# lesion-256.net
KiCad netlist of a schematic drawn in EAGLE
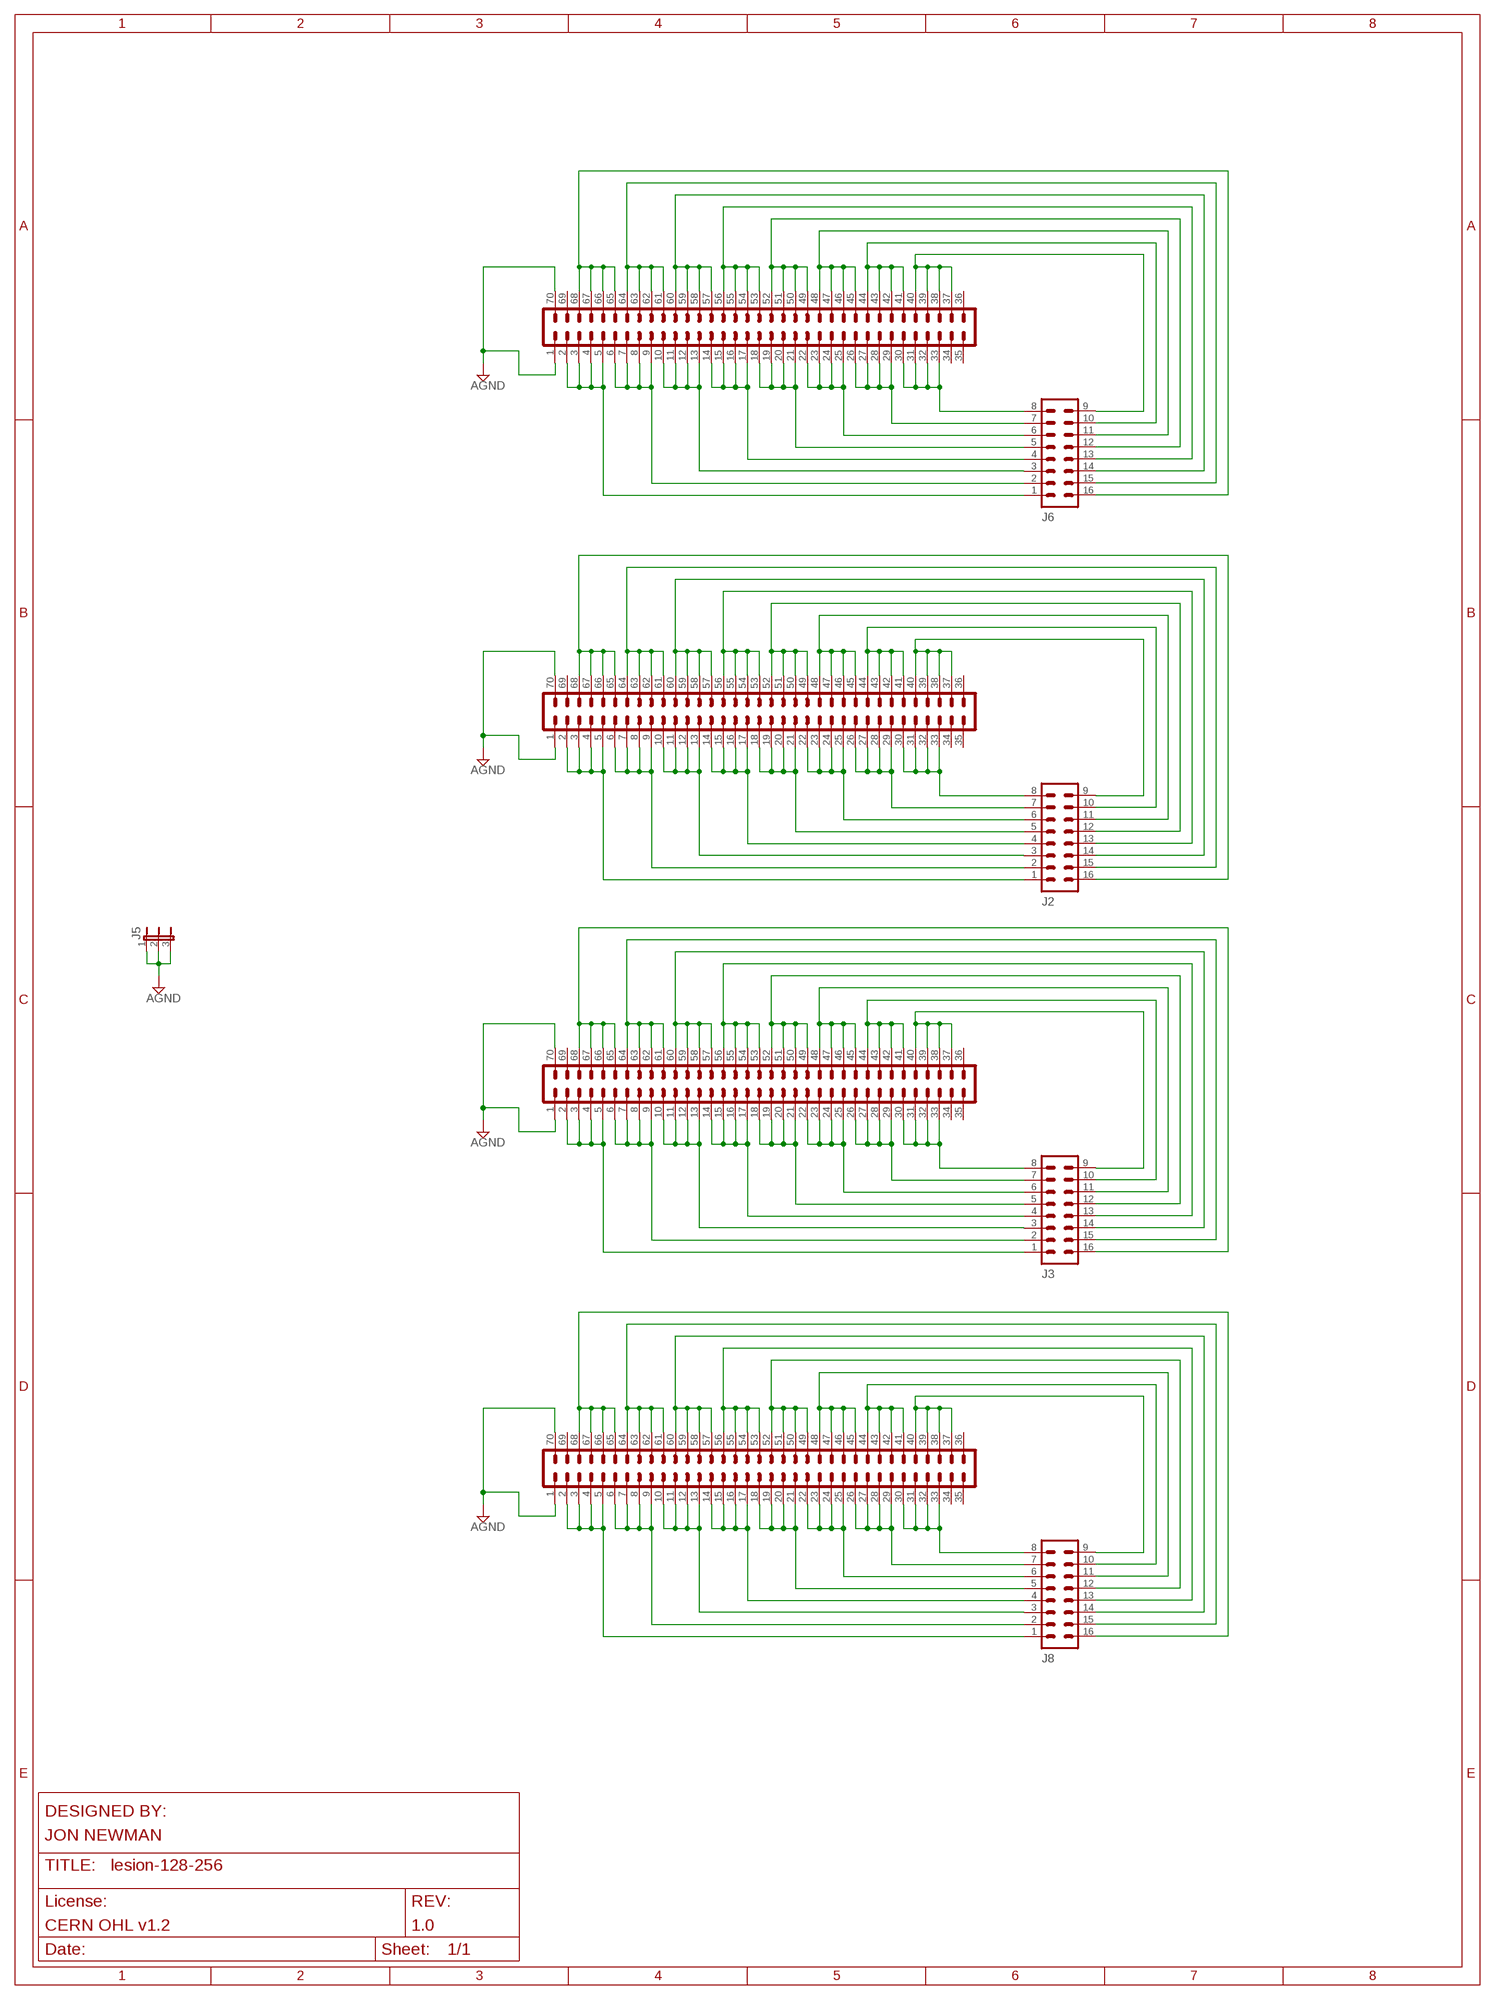
[diagram p0: schematic, sheet 1, part 1 of 2]
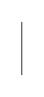
[diagram p1: schematic, sheet 1, part 2 of 2]

(export (version "E")
  (design (tool "Eeschema 10.0.6"))
  (components
    (comp (ref "J2")
      (value "PINHD-2X8_SMD_0.5\"")
      (footprint "eagle-import:JP2X8_SMD_0.5_")
      (libsource (lib "eagle-import") (part "PINHD-2X8_SMD_0.5{dblquote}"))
    )
    (comp (ref "J3")
      (value "PINHD-2X8_SMD_0.5\"")
      (footprint "eagle-import:JP2X8_SMD_0.5_")
      (libsource (lib "eagle-import") (part "PINHD-2X8_SMD_0.5{dblquote}"))
    )
    (comp (ref "J5")
      (value "JP3E_SMD-0.05")
      (footprint "eagle-import:JP3_SMD-0.05")
      (libsource (lib "eagle-import") (part "JP3E_SMD-0.05"))
    )
    (comp (ref "J6")
      (value "PINHD-2X8_SMD_0.5\"")
      (footprint "eagle-import:JP2X8_SMD_0.5_")
      (libsource (lib "eagle-import") (part "PINHD-2X8_SMD_0.5{dblquote}"))
    )
    (comp (ref "J8")
      (value "PINHD-2X8_SMD_0.5\"")
      (footprint "eagle-import:JP2X8_SMD_0.5_")
      (libsource (lib "eagle-import") (part "PINHD-2X8_SMD_0.5{dblquote}"))
    )
    (comp (ref "JA1")
      (value "DF40C(2.0)-70DS-0.4V(51)")
      (footprint "eagle-import:DF40-70REC")
      (libsource (lib "eagle-import") (part "PINHD-2X35_DF40REC"))
    )
    (comp (ref "JA3")
      (value "DF40C(2.0)-70DS-0.4V(51)")
      (footprint "eagle-import:DF40-70REC")
      (libsource (lib "eagle-import") (part "PINHD-2X35_DF40REC"))
    )
    (comp (ref "JA5")
      (value "DF40C(2.0)-70DS-0.4V(51)")
      (footprint "eagle-import:DF40-70REC")
      (libsource (lib "eagle-import") (part "PINHD-2X35_DF40REC"))
    )
    (comp (ref "JA7")
      (value "DF40C(2.0)-70DS-0.4V(51)")
      (footprint "eagle-import:DF40-70REC")
      (libsource (lib "eagle-import") (part "PINHD-2X35_DF40REC"))
    )
  )
  (nets
    (net (code "1") (name "AGND") (class "Default")
      (node (ref "J5") (pin "1") (pinfunction "1_1") (pintype "passive"))
      (node (ref "J5") (pin "2") (pinfunction "2_2") (pintype "passive"))
      (node (ref "J5") (pin "3") (pinfunction "3_3") (pintype "passive"))
      (node (ref "JA1") (pin "1") (pinfunction "1_1") (pintype "bidirectional"))
      (node (ref "JA1") (pin "70") (pinfunction "70_70") (pintype "bidirectional"))
      (node (ref "JA3") (pin "1") (pinfunction "1_1") (pintype "bidirectional"))
      (node (ref "JA3") (pin "70") (pinfunction "70_70") (pintype "bidirectional"))
      (node (ref "JA5") (pin "1") (pinfunction "1_1") (pintype "bidirectional"))
      (node (ref "JA5") (pin "70") (pinfunction "70_70") (pintype "bidirectional"))
      (node (ref "JA7") (pin "1") (pinfunction "1_1") (pintype "bidirectional"))
      (node (ref "JA7") (pin "70") (pinfunction "70_70") (pintype "bidirectional"))
    )
    (net (code "2") (name "Net-(J2-2)") (class "Default")
      (node (ref "J2") (pin "16") (pinfunction "2_16") (pintype "passive"))
      (node (ref "JA1") (pin "65") (pinfunction "65_65") (pintype "bidirectional"))
      (node (ref "JA1") (pin "66") (pinfunction "66_66") (pintype "bidirectional"))
      (node (ref "JA1") (pin "67") (pinfunction "67_67") (pintype "bidirectional"))
      (node (ref "JA1") (pin "68") (pinfunction "68_68") (pintype "bidirectional"))
    )
    (net (code "3") (name "Net-(J2-3)") (class "Default")
      (node (ref "J2") (pin "2") (pinfunction "3_2") (pintype "passive"))
      (node (ref "JA1") (pin "6") (pinfunction "6_6") (pintype "bidirectional"))
      (node (ref "JA1") (pin "7") (pinfunction "7_7") (pintype "bidirectional"))
      (node (ref "JA1") (pin "8") (pinfunction "8_8") (pintype "bidirectional"))
      (node (ref "JA1") (pin "9") (pinfunction "9_9") (pintype "bidirectional"))
    )
    (net (code "4") (name "Net-(J2-4)") (class "Default")
      (node (ref "J2") (pin "15") (pinfunction "4_15") (pintype "passive"))
      (node (ref "JA1") (pin "61") (pinfunction "61_61") (pintype "bidirectional"))
      (node (ref "JA1") (pin "62") (pinfunction "62_62") (pintype "bidirectional"))
      (node (ref "JA1") (pin "63") (pinfunction "63_63") (pintype "bidirectional"))
      (node (ref "JA1") (pin "64") (pinfunction "64_64") (pintype "bidirectional"))
    )
    (net (code "5") (name "Net-(J2-5)") (class "Default")
      (node (ref "J2") (pin "3") (pinfunction "5_3") (pintype "passive"))
      (node (ref "JA1") (pin "10") (pinfunction "10_10") (pintype "bidirectional"))
      (node (ref "JA1") (pin "11") (pinfunction "11_11") (pintype "bidirectional"))
      (node (ref "JA1") (pin "12") (pinfunction "12_12") (pintype "bidirectional"))
      (node (ref "JA1") (pin "13") (pinfunction "13_13") (pintype "bidirectional"))
    )
    (net (code "6") (name "Net-(J2-6)") (class "Default")
      (node (ref "J2") (pin "14") (pinfunction "6_14") (pintype "passive"))
      (node (ref "JA1") (pin "57") (pinfunction "57_57") (pintype "bidirectional"))
      (node (ref "JA1") (pin "58") (pinfunction "58_58") (pintype "bidirectional"))
      (node (ref "JA1") (pin "59") (pinfunction "59_59") (pintype "bidirectional"))
      (node (ref "JA1") (pin "60") (pinfunction "60_60") (pintype "bidirectional"))
    )
    (net (code "7") (name "Net-(J2-7)") (class "Default")
      (node (ref "J2") (pin "4") (pinfunction "7_4") (pintype "passive"))
      (node (ref "JA1") (pin "14") (pinfunction "14_14") (pintype "bidirectional"))
      (node (ref "JA1") (pin "15") (pinfunction "15_15") (pintype "bidirectional"))
      (node (ref "JA1") (pin "16") (pinfunction "16_16") (pintype "bidirectional"))
      (node (ref "JA1") (pin "17") (pinfunction "17_17") (pintype "bidirectional"))
    )
    (net (code "8") (name "Net-(J2-8)") (class "Default")
      (node (ref "J2") (pin "13") (pinfunction "8_13") (pintype "passive"))
      (node (ref "JA1") (pin "53") (pinfunction "53_53") (pintype "bidirectional"))
      (node (ref "JA1") (pin "54") (pinfunction "54_54") (pintype "bidirectional"))
      (node (ref "JA1") (pin "55") (pinfunction "55_55") (pintype "bidirectional"))
      (node (ref "JA1") (pin "56") (pinfunction "56_56") (pintype "bidirectional"))
    )
    (net (code "9") (name "Net-(J2-9)") (class "Default")
      (node (ref "J2") (pin "5") (pinfunction "9_5") (pintype "passive"))
      (node (ref "JA1") (pin "18") (pinfunction "18_18") (pintype "bidirectional"))
      (node (ref "JA1") (pin "19") (pinfunction "19_19") (pintype "bidirectional"))
      (node (ref "JA1") (pin "20") (pinfunction "20_20") (pintype "bidirectional"))
      (node (ref "JA1") (pin "21") (pinfunction "21_21") (pintype "bidirectional"))
    )
    (net (code "10") (name "Net-(J2-10)") (class "Default")
      (node (ref "J2") (pin "12") (pinfunction "10_12") (pintype "passive"))
      (node (ref "JA1") (pin "49") (pinfunction "49_49") (pintype "bidirectional"))
      (node (ref "JA1") (pin "50") (pinfunction "50_50") (pintype "bidirectional"))
      (node (ref "JA1") (pin "51") (pinfunction "51_51") (pintype "bidirectional"))
      (node (ref "JA1") (pin "52") (pinfunction "52_52") (pintype "bidirectional"))
    )
    (net (code "11") (name "Net-(J2-11)") (class "Default")
      (node (ref "J2") (pin "6") (pinfunction "11_6") (pintype "passive"))
      (node (ref "JA1") (pin "22") (pinfunction "22_22") (pintype "bidirectional"))
      (node (ref "JA1") (pin "23") (pinfunction "23_23") (pintype "bidirectional"))
      (node (ref "JA1") (pin "24") (pinfunction "24_24") (pintype "bidirectional"))
      (node (ref "JA1") (pin "25") (pinfunction "25_25") (pintype "bidirectional"))
    )
    (net (code "12") (name "Net-(J2-12)") (class "Default")
      (node (ref "J2") (pin "11") (pinfunction "12_11") (pintype "passive"))
      (node (ref "JA1") (pin "45") (pinfunction "45_45") (pintype "bidirectional"))
      (node (ref "JA1") (pin "46") (pinfunction "46_46") (pintype "bidirectional"))
      (node (ref "JA1") (pin "47") (pinfunction "47_47") (pintype "bidirectional"))
      (node (ref "JA1") (pin "48") (pinfunction "48_48") (pintype "bidirectional"))
    )
    (net (code "13") (name "Net-(J2-13)") (class "Default")
      (node (ref "J2") (pin "7") (pinfunction "13_7") (pintype "passive"))
      (node (ref "JA1") (pin "26") (pinfunction "26_26") (pintype "bidirectional"))
      (node (ref "JA1") (pin "27") (pinfunction "27_27") (pintype "bidirectional"))
      (node (ref "JA1") (pin "28") (pinfunction "28_28") (pintype "bidirectional"))
      (node (ref "JA1") (pin "29") (pinfunction "29_29") (pintype "bidirectional"))
    )
    (net (code "14") (name "Net-(J2-14)") (class "Default")
      (node (ref "J2") (pin "10") (pinfunction "14_10") (pintype "passive"))
      (node (ref "JA1") (pin "41") (pinfunction "41_41") (pintype "bidirectional"))
      (node (ref "JA1") (pin "42") (pinfunction "42_42") (pintype "bidirectional"))
      (node (ref "JA1") (pin "43") (pinfunction "43_43") (pintype "bidirectional"))
      (node (ref "JA1") (pin "44") (pinfunction "44_44") (pintype "bidirectional"))
    )
    (net (code "15") (name "Net-(J2-15)") (class "Default")
      (node (ref "J2") (pin "8") (pinfunction "15_8") (pintype "passive"))
      (node (ref "JA1") (pin "30") (pinfunction "30_30") (pintype "bidirectional"))
      (node (ref "JA1") (pin "31") (pinfunction "31_31") (pintype "bidirectional"))
      (node (ref "JA1") (pin "32") (pinfunction "32_32") (pintype "bidirectional"))
      (node (ref "JA1") (pin "33") (pinfunction "33_33") (pintype "bidirectional"))
    )
    (net (code "16") (name "Net-(J2-16)") (class "Default")
      (node (ref "J2") (pin "9") (pinfunction "16_9") (pintype "passive"))
      (node (ref "JA1") (pin "37") (pinfunction "37_37") (pintype "bidirectional"))
      (node (ref "JA1") (pin "38") (pinfunction "38_38") (pintype "bidirectional"))
      (node (ref "JA1") (pin "39") (pinfunction "39_39") (pintype "bidirectional"))
      (node (ref "JA1") (pin "40") (pinfunction "40_40") (pintype "bidirectional"))
    )
    (net (code "17") (name "Net-(J2-Pad1)") (class "Default")
      (node (ref "J2") (pin "1") (pinfunction "1_1") (pintype "passive"))
      (node (ref "JA1") (pin "2") (pinfunction "2_2") (pintype "bidirectional"))
      (node (ref "JA1") (pin "3") (pinfunction "3_3") (pintype "bidirectional"))
      (node (ref "JA1") (pin "4") (pinfunction "4_4") (pintype "bidirectional"))
      (node (ref "JA1") (pin "5") (pinfunction "5_5") (pintype "bidirectional"))
    )
    (net (code "18") (name "Net-(J3-2)") (class "Default")
      (node (ref "J3") (pin "16") (pinfunction "2_16") (pintype "passive"))
      (node (ref "JA3") (pin "65") (pinfunction "65_65") (pintype "bidirectional"))
      (node (ref "JA3") (pin "66") (pinfunction "66_66") (pintype "bidirectional"))
      (node (ref "JA3") (pin "67") (pinfunction "67_67") (pintype "bidirectional"))
      (node (ref "JA3") (pin "68") (pinfunction "68_68") (pintype "bidirectional"))
    )
    (net (code "19") (name "Net-(J3-3)") (class "Default")
      (node (ref "J3") (pin "2") (pinfunction "3_2") (pintype "passive"))
      (node (ref "JA3") (pin "6") (pinfunction "6_6") (pintype "bidirectional"))
      (node (ref "JA3") (pin "7") (pinfunction "7_7") (pintype "bidirectional"))
      (node (ref "JA3") (pin "8") (pinfunction "8_8") (pintype "bidirectional"))
      (node (ref "JA3") (pin "9") (pinfunction "9_9") (pintype "bidirectional"))
    )
    (net (code "20") (name "Net-(J3-4)") (class "Default")
      (node (ref "J3") (pin "15") (pinfunction "4_15") (pintype "passive"))
      (node (ref "JA3") (pin "61") (pinfunction "61_61") (pintype "bidirectional"))
      (node (ref "JA3") (pin "62") (pinfunction "62_62") (pintype "bidirectional"))
      (node (ref "JA3") (pin "63") (pinfunction "63_63") (pintype "bidirectional"))
      (node (ref "JA3") (pin "64") (pinfunction "64_64") (pintype "bidirectional"))
    )
    (net (code "21") (name "Net-(J3-5)") (class "Default")
      (node (ref "J3") (pin "3") (pinfunction "5_3") (pintype "passive"))
      (node (ref "JA3") (pin "10") (pinfunction "10_10") (pintype "bidirectional"))
      (node (ref "JA3") (pin "11") (pinfunction "11_11") (pintype "bidirectional"))
      (node (ref "JA3") (pin "12") (pinfunction "12_12") (pintype "bidirectional"))
      (node (ref "JA3") (pin "13") (pinfunction "13_13") (pintype "bidirectional"))
    )
    (net (code "22") (name "Net-(J3-6)") (class "Default")
      (node (ref "J3") (pin "14") (pinfunction "6_14") (pintype "passive"))
      (node (ref "JA3") (pin "57") (pinfunction "57_57") (pintype "bidirectional"))
      (node (ref "JA3") (pin "58") (pinfunction "58_58") (pintype "bidirectional"))
      (node (ref "JA3") (pin "59") (pinfunction "59_59") (pintype "bidirectional"))
      (node (ref "JA3") (pin "60") (pinfunction "60_60") (pintype "bidirectional"))
    )
    (net (code "23") (name "Net-(J3-7)") (class "Default")
      (node (ref "J3") (pin "4") (pinfunction "7_4") (pintype "passive"))
      (node (ref "JA3") (pin "14") (pinfunction "14_14") (pintype "bidirectional"))
      (node (ref "JA3") (pin "15") (pinfunction "15_15") (pintype "bidirectional"))
      (node (ref "JA3") (pin "16") (pinfunction "16_16") (pintype "bidirectional"))
      (node (ref "JA3") (pin "17") (pinfunction "17_17") (pintype "bidirectional"))
    )
    (net (code "24") (name "Net-(J3-8)") (class "Default")
      (node (ref "J3") (pin "13") (pinfunction "8_13") (pintype "passive"))
      (node (ref "JA3") (pin "53") (pinfunction "53_53") (pintype "bidirectional"))
      (node (ref "JA3") (pin "54") (pinfunction "54_54") (pintype "bidirectional"))
      (node (ref "JA3") (pin "55") (pinfunction "55_55") (pintype "bidirectional"))
      (node (ref "JA3") (pin "56") (pinfunction "56_56") (pintype "bidirectional"))
    )
    (net (code "25") (name "Net-(J3-9)") (class "Default")
      (node (ref "J3") (pin "5") (pinfunction "9_5") (pintype "passive"))
      (node (ref "JA3") (pin "18") (pinfunction "18_18") (pintype "bidirectional"))
      (node (ref "JA3") (pin "19") (pinfunction "19_19") (pintype "bidirectional"))
      (node (ref "JA3") (pin "20") (pinfunction "20_20") (pintype "bidirectional"))
      (node (ref "JA3") (pin "21") (pinfunction "21_21") (pintype "bidirectional"))
    )
    (net (code "26") (name "Net-(J3-10)") (class "Default")
      (node (ref "J3") (pin "12") (pinfunction "10_12") (pintype "passive"))
      (node (ref "JA3") (pin "49") (pinfunction "49_49") (pintype "bidirectional"))
      (node (ref "JA3") (pin "50") (pinfunction "50_50") (pintype "bidirectional"))
      (node (ref "JA3") (pin "51") (pinfunction "51_51") (pintype "bidirectional"))
      (node (ref "JA3") (pin "52") (pinfunction "52_52") (pintype "bidirectional"))
    )
    (net (code "27") (name "Net-(J3-11)") (class "Default")
      (node (ref "J3") (pin "6") (pinfunction "11_6") (pintype "passive"))
      (node (ref "JA3") (pin "22") (pinfunction "22_22") (pintype "bidirectional"))
      (node (ref "JA3") (pin "23") (pinfunction "23_23") (pintype "bidirectional"))
      (node (ref "JA3") (pin "24") (pinfunction "24_24") (pintype "bidirectional"))
      (node (ref "JA3") (pin "25") (pinfunction "25_25") (pintype "bidirectional"))
    )
    (net (code "28") (name "Net-(J3-12)") (class "Default")
      (node (ref "J3") (pin "11") (pinfunction "12_11") (pintype "passive"))
      (node (ref "JA3") (pin "45") (pinfunction "45_45") (pintype "bidirectional"))
      (node (ref "JA3") (pin "46") (pinfunction "46_46") (pintype "bidirectional"))
      (node (ref "JA3") (pin "47") (pinfunction "47_47") (pintype "bidirectional"))
      (node (ref "JA3") (pin "48") (pinfunction "48_48") (pintype "bidirectional"))
    )
    (net (code "29") (name "Net-(J3-13)") (class "Default")
      (node (ref "J3") (pin "7") (pinfunction "13_7") (pintype "passive"))
      (node (ref "JA3") (pin "26") (pinfunction "26_26") (pintype "bidirectional"))
      (node (ref "JA3") (pin "27") (pinfunction "27_27") (pintype "bidirectional"))
      (node (ref "JA3") (pin "28") (pinfunction "28_28") (pintype "bidirectional"))
      (node (ref "JA3") (pin "29") (pinfunction "29_29") (pintype "bidirectional"))
    )
    (net (code "30") (name "Net-(J3-14)") (class "Default")
      (node (ref "J3") (pin "10") (pinfunction "14_10") (pintype "passive"))
      (node (ref "JA3") (pin "41") (pinfunction "41_41") (pintype "bidirectional"))
      (node (ref "JA3") (pin "42") (pinfunction "42_42") (pintype "bidirectional"))
      (node (ref "JA3") (pin "43") (pinfunction "43_43") (pintype "bidirectional"))
      (node (ref "JA3") (pin "44") (pinfunction "44_44") (pintype "bidirectional"))
    )
    (net (code "31") (name "Net-(J3-15)") (class "Default")
      (node (ref "J3") (pin "8") (pinfunction "15_8") (pintype "passive"))
      (node (ref "JA3") (pin "30") (pinfunction "30_30") (pintype "bidirectional"))
      (node (ref "JA3") (pin "31") (pinfunction "31_31") (pintype "bidirectional"))
      (node (ref "JA3") (pin "32") (pinfunction "32_32") (pintype "bidirectional"))
      (node (ref "JA3") (pin "33") (pinfunction "33_33") (pintype "bidirectional"))
    )
    (net (code "32") (name "Net-(J3-16)") (class "Default")
      (node (ref "J3") (pin "9") (pinfunction "16_9") (pintype "passive"))
      (node (ref "JA3") (pin "37") (pinfunction "37_37") (pintype "bidirectional"))
      (node (ref "JA3") (pin "38") (pinfunction "38_38") (pintype "bidirectional"))
      (node (ref "JA3") (pin "39") (pinfunction "39_39") (pintype "bidirectional"))
      (node (ref "JA3") (pin "40") (pinfunction "40_40") (pintype "bidirectional"))
    )
    (net (code "33") (name "Net-(J3-Pad1)") (class "Default")
      (node (ref "J3") (pin "1") (pinfunction "1_1") (pintype "passive"))
      (node (ref "JA3") (pin "2") (pinfunction "2_2") (pintype "bidirectional"))
      (node (ref "JA3") (pin "3") (pinfunction "3_3") (pintype "bidirectional"))
      (node (ref "JA3") (pin "4") (pinfunction "4_4") (pintype "bidirectional"))
      (node (ref "JA3") (pin "5") (pinfunction "5_5") (pintype "bidirectional"))
    )
    (net (code "34") (name "Net-(J6-2)") (class "Default")
      (node (ref "J6") (pin "16") (pinfunction "2_16") (pintype "passive"))
      (node (ref "JA5") (pin "65") (pinfunction "65_65") (pintype "bidirectional"))
      (node (ref "JA5") (pin "66") (pinfunction "66_66") (pintype "bidirectional"))
      (node (ref "JA5") (pin "67") (pinfunction "67_67") (pintype "bidirectional"))
      (node (ref "JA5") (pin "68") (pinfunction "68_68") (pintype "bidirectional"))
    )
    (net (code "35") (name "Net-(J6-3)") (class "Default")
      (node (ref "J6") (pin "2") (pinfunction "3_2") (pintype "passive"))
      (node (ref "JA5") (pin "6") (pinfunction "6_6") (pintype "bidirectional"))
      (node (ref "JA5") (pin "7") (pinfunction "7_7") (pintype "bidirectional"))
      (node (ref "JA5") (pin "8") (pinfunction "8_8") (pintype "bidirectional"))
      (node (ref "JA5") (pin "9") (pinfunction "9_9") (pintype "bidirectional"))
    )
    (net (code "36") (name "Net-(J6-4)") (class "Default")
      (node (ref "J6") (pin "15") (pinfunction "4_15") (pintype "passive"))
      (node (ref "JA5") (pin "61") (pinfunction "61_61") (pintype "bidirectional"))
      (node (ref "JA5") (pin "62") (pinfunction "62_62") (pintype "bidirectional"))
      (node (ref "JA5") (pin "63") (pinfunction "63_63") (pintype "bidirectional"))
      (node (ref "JA5") (pin "64") (pinfunction "64_64") (pintype "bidirectional"))
    )
    (net (code "37") (name "Net-(J6-5)") (class "Default")
      (node (ref "J6") (pin "3") (pinfunction "5_3") (pintype "passive"))
      (node (ref "JA5") (pin "10") (pinfunction "10_10") (pintype "bidirectional"))
      (node (ref "JA5") (pin "11") (pinfunction "11_11") (pintype "bidirectional"))
      (node (ref "JA5") (pin "12") (pinfunction "12_12") (pintype "bidirectional"))
      (node (ref "JA5") (pin "13") (pinfunction "13_13") (pintype "bidirectional"))
    )
    (net (code "38") (name "Net-(J6-6)") (class "Default")
      (node (ref "J6") (pin "14") (pinfunction "6_14") (pintype "passive"))
      (node (ref "JA5") (pin "57") (pinfunction "57_57") (pintype "bidirectional"))
      (node (ref "JA5") (pin "58") (pinfunction "58_58") (pintype "bidirectional"))
      (node (ref "JA5") (pin "59") (pinfunction "59_59") (pintype "bidirectional"))
      (node (ref "JA5") (pin "60") (pinfunction "60_60") (pintype "bidirectional"))
    )
    (net (code "39") (name "Net-(J6-7)") (class "Default")
      (node (ref "J6") (pin "4") (pinfunction "7_4") (pintype "passive"))
      (node (ref "JA5") (pin "14") (pinfunction "14_14") (pintype "bidirectional"))
      (node (ref "JA5") (pin "15") (pinfunction "15_15") (pintype "bidirectional"))
      (node (ref "JA5") (pin "16") (pinfunction "16_16") (pintype "bidirectional"))
      (node (ref "JA5") (pin "17") (pinfunction "17_17") (pintype "bidirectional"))
    )
    (net (code "40") (name "Net-(J6-8)") (class "Default")
      (node (ref "J6") (pin "13") (pinfunction "8_13") (pintype "passive"))
      (node (ref "JA5") (pin "53") (pinfunction "53_53") (pintype "bidirectional"))
      (node (ref "JA5") (pin "54") (pinfunction "54_54") (pintype "bidirectional"))
      (node (ref "JA5") (pin "55") (pinfunction "55_55") (pintype "bidirectional"))
      (node (ref "JA5") (pin "56") (pinfunction "56_56") (pintype "bidirectional"))
    )
    (net (code "41") (name "Net-(J6-9)") (class "Default")
      (node (ref "J6") (pin "5") (pinfunction "9_5") (pintype "passive"))
      (node (ref "JA5") (pin "18") (pinfunction "18_18") (pintype "bidirectional"))
      (node (ref "JA5") (pin "19") (pinfunction "19_19") (pintype "bidirectional"))
      (node (ref "JA5") (pin "20") (pinfunction "20_20") (pintype "bidirectional"))
      (node (ref "JA5") (pin "21") (pinfunction "21_21") (pintype "bidirectional"))
    )
    (net (code "42") (name "Net-(J6-10)") (class "Default")
      (node (ref "J6") (pin "12") (pinfunction "10_12") (pintype "passive"))
      (node (ref "JA5") (pin "49") (pinfunction "49_49") (pintype "bidirectional"))
      (node (ref "JA5") (pin "50") (pinfunction "50_50") (pintype "bidirectional"))
      (node (ref "JA5") (pin "51") (pinfunction "51_51") (pintype "bidirectional"))
      (node (ref "JA5") (pin "52") (pinfunction "52_52") (pintype "bidirectional"))
    )
    (net (code "43") (name "Net-(J6-11)") (class "Default")
      (node (ref "J6") (pin "6") (pinfunction "11_6") (pintype "passive"))
      (node (ref "JA5") (pin "22") (pinfunction "22_22") (pintype "bidirectional"))
      (node (ref "JA5") (pin "23") (pinfunction "23_23") (pintype "bidirectional"))
      (node (ref "JA5") (pin "24") (pinfunction "24_24") (pintype "bidirectional"))
      (node (ref "JA5") (pin "25") (pinfunction "25_25") (pintype "bidirectional"))
    )
    (net (code "44") (name "Net-(J6-12)") (class "Default")
      (node (ref "J6") (pin "11") (pinfunction "12_11") (pintype "passive"))
      (node (ref "JA5") (pin "45") (pinfunction "45_45") (pintype "bidirectional"))
      (node (ref "JA5") (pin "46") (pinfunction "46_46") (pintype "bidirectional"))
      (node (ref "JA5") (pin "47") (pinfunction "47_47") (pintype "bidirectional"))
      (node (ref "JA5") (pin "48") (pinfunction "48_48") (pintype "bidirectional"))
    )
    (net (code "45") (name "Net-(J6-13)") (class "Default")
      (node (ref "J6") (pin "7") (pinfunction "13_7") (pintype "passive"))
      (node (ref "JA5") (pin "26") (pinfunction "26_26") (pintype "bidirectional"))
      (node (ref "JA5") (pin "27") (pinfunction "27_27") (pintype "bidirectional"))
      (node (ref "JA5") (pin "28") (pinfunction "28_28") (pintype "bidirectional"))
      (node (ref "JA5") (pin "29") (pinfunction "29_29") (pintype "bidirectional"))
    )
    (net (code "46") (name "Net-(J6-14)") (class "Default")
      (node (ref "J6") (pin "10") (pinfunction "14_10") (pintype "passive"))
      (node (ref "JA5") (pin "41") (pinfunction "41_41") (pintype "bidirectional"))
      (node (ref "JA5") (pin "42") (pinfunction "42_42") (pintype "bidirectional"))
      (node (ref "JA5") (pin "43") (pinfunction "43_43") (pintype "bidirectional"))
      (node (ref "JA5") (pin "44") (pinfunction "44_44") (pintype "bidirectional"))
    )
    (net (code "47") (name "Net-(J6-15)") (class "Default")
      (node (ref "J6") (pin "8") (pinfunction "15_8") (pintype "passive"))
      (node (ref "JA5") (pin "30") (pinfunction "30_30") (pintype "bidirectional"))
      (node (ref "JA5") (pin "31") (pinfunction "31_31") (pintype "bidirectional"))
      (node (ref "JA5") (pin "32") (pinfunction "32_32") (pintype "bidirectional"))
      (node (ref "JA5") (pin "33") (pinfunction "33_33") (pintype "bidirectional"))
    )
    (net (code "48") (name "Net-(J6-16)") (class "Default")
      (node (ref "J6") (pin "9") (pinfunction "16_9") (pintype "passive"))
      (node (ref "JA5") (pin "37") (pinfunction "37_37") (pintype "bidirectional"))
      (node (ref "JA5") (pin "38") (pinfunction "38_38") (pintype "bidirectional"))
      (node (ref "JA5") (pin "39") (pinfunction "39_39") (pintype "bidirectional"))
      (node (ref "JA5") (pin "40") (pinfunction "40_40") (pintype "bidirectional"))
    )
    (net (code "49") (name "Net-(J6-Pad1)") (class "Default")
      (node (ref "J6") (pin "1") (pinfunction "1_1") (pintype "passive"))
      (node (ref "JA5") (pin "2") (pinfunction "2_2") (pintype "bidirectional"))
      (node (ref "JA5") (pin "3") (pinfunction "3_3") (pintype "bidirectional"))
      (node (ref "JA5") (pin "4") (pinfunction "4_4") (pintype "bidirectional"))
      (node (ref "JA5") (pin "5") (pinfunction "5_5") (pintype "bidirectional"))
    )
    (net (code "50") (name "Net-(J8-2)") (class "Default")
      (node (ref "J8") (pin "16") (pinfunction "2_16") (pintype "passive"))
      (node (ref "JA7") (pin "65") (pinfunction "65_65") (pintype "bidirectional"))
      (node (ref "JA7") (pin "66") (pinfunction "66_66") (pintype "bidirectional"))
      (node (ref "JA7") (pin "67") (pinfunction "67_67") (pintype "bidirectional"))
      (node (ref "JA7") (pin "68") (pinfunction "68_68") (pintype "bidirectional"))
    )
    (net (code "51") (name "Net-(J8-3)") (class "Default")
      (node (ref "J8") (pin "2") (pinfunction "3_2") (pintype "passive"))
      (node (ref "JA7") (pin "6") (pinfunction "6_6") (pintype "bidirectional"))
      (node (ref "JA7") (pin "7") (pinfunction "7_7") (pintype "bidirectional"))
      (node (ref "JA7") (pin "8") (pinfunction "8_8") (pintype "bidirectional"))
      (node (ref "JA7") (pin "9") (pinfunction "9_9") (pintype "bidirectional"))
    )
    (net (code "52") (name "Net-(J8-4)") (class "Default")
      (node (ref "J8") (pin "15") (pinfunction "4_15") (pintype "passive"))
      (node (ref "JA7") (pin "61") (pinfunction "61_61") (pintype "bidirectional"))
      (node (ref "JA7") (pin "62") (pinfunction "62_62") (pintype "bidirectional"))
      (node (ref "JA7") (pin "63") (pinfunction "63_63") (pintype "bidirectional"))
      (node (ref "JA7") (pin "64") (pinfunction "64_64") (pintype "bidirectional"))
    )
    (net (code "53") (name "Net-(J8-5)") (class "Default")
      (node (ref "J8") (pin "3") (pinfunction "5_3") (pintype "passive"))
      (node (ref "JA7") (pin "10") (pinfunction "10_10") (pintype "bidirectional"))
      (node (ref "JA7") (pin "11") (pinfunction "11_11") (pintype "bidirectional"))
      (node (ref "JA7") (pin "12") (pinfunction "12_12") (pintype "bidirectional"))
      (node (ref "JA7") (pin "13") (pinfunction "13_13") (pintype "bidirectional"))
    )
    (net (code "54") (name "Net-(J8-6)") (class "Default")
      (node (ref "J8") (pin "14") (pinfunction "6_14") (pintype "passive"))
      (node (ref "JA7") (pin "57") (pinfunction "57_57") (pintype "bidirectional"))
      (node (ref "JA7") (pin "58") (pinfunction "58_58") (pintype "bidirectional"))
      (node (ref "JA7") (pin "59") (pinfunction "59_59") (pintype "bidirectional"))
      (node (ref "JA7") (pin "60") (pinfunction "60_60") (pintype "bidirectional"))
    )
    (net (code "55") (name "Net-(J8-7)") (class "Default")
      (node (ref "J8") (pin "4") (pinfunction "7_4") (pintype "passive"))
      (node (ref "JA7") (pin "14") (pinfunction "14_14") (pintype "bidirectional"))
      (node (ref "JA7") (pin "15") (pinfunction "15_15") (pintype "bidirectional"))
      (node (ref "JA7") (pin "16") (pinfunction "16_16") (pintype "bidirectional"))
      (node (ref "JA7") (pin "17") (pinfunction "17_17") (pintype "bidirectional"))
    )
    (net (code "56") (name "Net-(J8-8)") (class "Default")
      (node (ref "J8") (pin "13") (pinfunction "8_13") (pintype "passive"))
      (node (ref "JA7") (pin "53") (pinfunction "53_53") (pintype "bidirectional"))
      (node (ref "JA7") (pin "54") (pinfunction "54_54") (pintype "bidirectional"))
      (node (ref "JA7") (pin "55") (pinfunction "55_55") (pintype "bidirectional"))
      (node (ref "JA7") (pin "56") (pinfunction "56_56") (pintype "bidirectional"))
    )
    (net (code "57") (name "Net-(J8-9)") (class "Default")
      (node (ref "J8") (pin "5") (pinfunction "9_5") (pintype "passive"))
      (node (ref "JA7") (pin "18") (pinfunction "18_18") (pintype "bidirectional"))
      (node (ref "JA7") (pin "19") (pinfunction "19_19") (pintype "bidirectional"))
      (node (ref "JA7") (pin "20") (pinfunction "20_20") (pintype "bidirectional"))
      (node (ref "JA7") (pin "21") (pinfunction "21_21") (pintype "bidirectional"))
    )
    (net (code "58") (name "Net-(J8-10)") (class "Default")
      (node (ref "J8") (pin "12") (pinfunction "10_12") (pintype "passive"))
      (node (ref "JA7") (pin "49") (pinfunction "49_49") (pintype "bidirectional"))
      (node (ref "JA7") (pin "50") (pinfunction "50_50") (pintype "bidirectional"))
      (node (ref "JA7") (pin "51") (pinfunction "51_51") (pintype "bidirectional"))
      (node (ref "JA7") (pin "52") (pinfunction "52_52") (pintype "bidirectional"))
    )
    (net (code "59") (name "Net-(J8-11)") (class "Default")
      (node (ref "J8") (pin "6") (pinfunction "11_6") (pintype "passive"))
      (node (ref "JA7") (pin "22") (pinfunction "22_22") (pintype "bidirectional"))
      (node (ref "JA7") (pin "23") (pinfunction "23_23") (pintype "bidirectional"))
      (node (ref "JA7") (pin "24") (pinfunction "24_24") (pintype "bidirectional"))
      (node (ref "JA7") (pin "25") (pinfunction "25_25") (pintype "bidirectional"))
    )
    (net (code "60") (name "Net-(J8-12)") (class "Default")
      (node (ref "J8") (pin "11") (pinfunction "12_11") (pintype "passive"))
      (node (ref "JA7") (pin "45") (pinfunction "45_45") (pintype "bidirectional"))
      (node (ref "JA7") (pin "46") (pinfunction "46_46") (pintype "bidirectional"))
      (node (ref "JA7") (pin "47") (pinfunction "47_47") (pintype "bidirectional"))
      (node (ref "JA7") (pin "48") (pinfunction "48_48") (pintype "bidirectional"))
    )
    (net (code "61") (name "Net-(J8-13)") (class "Default")
      (node (ref "J8") (pin "7") (pinfunction "13_7") (pintype "passive"))
      (node (ref "JA7") (pin "26") (pinfunction "26_26") (pintype "bidirectional"))
      (node (ref "JA7") (pin "27") (pinfunction "27_27") (pintype "bidirectional"))
      (node (ref "JA7") (pin "28") (pinfunction "28_28") (pintype "bidirectional"))
      (node (ref "JA7") (pin "29") (pinfunction "29_29") (pintype "bidirectional"))
    )
    (net (code "62") (name "Net-(J8-14)") (class "Default")
      (node (ref "J8") (pin "10") (pinfunction "14_10") (pintype "passive"))
      (node (ref "JA7") (pin "41") (pinfunction "41_41") (pintype "bidirectional"))
      (node (ref "JA7") (pin "42") (pinfunction "42_42") (pintype "bidirectional"))
      (node (ref "JA7") (pin "43") (pinfunction "43_43") (pintype "bidirectional"))
      (node (ref "JA7") (pin "44") (pinfunction "44_44") (pintype "bidirectional"))
    )
    (net (code "63") (name "Net-(J8-15)") (class "Default")
      (node (ref "J8") (pin "8") (pinfunction "15_8") (pintype "passive"))
      (node (ref "JA7") (pin "30") (pinfunction "30_30") (pintype "bidirectional"))
      (node (ref "JA7") (pin "31") (pinfunction "31_31") (pintype "bidirectional"))
      (node (ref "JA7") (pin "32") (pinfunction "32_32") (pintype "bidirectional"))
      (node (ref "JA7") (pin "33") (pinfunction "33_33") (pintype "bidirectional"))
    )
    (net (code "64") (name "Net-(J8-16)") (class "Default")
      (node (ref "J8") (pin "9") (pinfunction "16_9") (pintype "passive"))
      (node (ref "JA7") (pin "37") (pinfunction "37_37") (pintype "bidirectional"))
      (node (ref "JA7") (pin "38") (pinfunction "38_38") (pintype "bidirectional"))
      (node (ref "JA7") (pin "39") (pinfunction "39_39") (pintype "bidirectional"))
      (node (ref "JA7") (pin "40") (pinfunction "40_40") (pintype "bidirectional"))
    )
    (net (code "65") (name "Net-(J8-Pad1)") (class "Default")
      (node (ref "J8") (pin "1") (pinfunction "1_1") (pintype "passive"))
      (node (ref "JA7") (pin "2") (pinfunction "2_2") (pintype "bidirectional"))
      (node (ref "JA7") (pin "3") (pinfunction "3_3") (pintype "bidirectional"))
      (node (ref "JA7") (pin "4") (pinfunction "4_4") (pintype "bidirectional"))
      (node (ref "JA7") (pin "5") (pinfunction "5_5") (pintype "bidirectional"))
    )
    (net (code "66") (name "unconnected-(JA1-Pad34)") (class "Default")
      (node (ref "JA1") (pin "34") (pinfunction "34_34") (pintype "bidirectional"))
    )
    (net (code "67") (name "unconnected-(JA1-Pad35)") (class "Default")
      (node (ref "JA1") (pin "35") (pinfunction "35_35") (pintype "bidirectional"))
    )
    (net (code "68") (name "unconnected-(JA1-Pad36)") (class "Default")
      (node (ref "JA1") (pin "36") (pinfunction "36_36") (pintype "bidirectional"))
    )
    (net (code "69") (name "unconnected-(JA1-Pad69)") (class "Default")
      (node (ref "JA1") (pin "69") (pinfunction "69_69") (pintype "bidirectional"))
    )
    (net (code "70") (name "unconnected-(JA3-Pad34)") (class "Default")
      (node (ref "JA3") (pin "34") (pinfunction "34_34") (pintype "bidirectional"))
    )
    (net (code "71") (name "unconnected-(JA3-Pad35)") (class "Default")
      (node (ref "JA3") (pin "35") (pinfunction "35_35") (pintype "bidirectional"))
    )
    (net (code "72") (name "unconnected-(JA3-Pad36)") (class "Default")
      (node (ref "JA3") (pin "36") (pinfunction "36_36") (pintype "bidirectional"))
    )
    (net (code "73") (name "unconnected-(JA3-Pad69)") (class "Default")
      (node (ref "JA3") (pin "69") (pinfunction "69_69") (pintype "bidirectional"))
    )
    (net (code "74") (name "unconnected-(JA5-Pad34)") (class "Default")
      (node (ref "JA5") (pin "34") (pinfunction "34_34") (pintype "bidirectional"))
    )
    (net (code "75") (name "unconnected-(JA5-Pad35)") (class "Default")
      (node (ref "JA5") (pin "35") (pinfunction "35_35") (pintype "bidirectional"))
    )
    (net (code "76") (name "unconnected-(JA5-Pad36)") (class "Default")
      (node (ref "JA5") (pin "36") (pinfunction "36_36") (pintype "bidirectional"))
    )
    (net (code "77") (name "unconnected-(JA5-Pad69)") (class "Default")
      (node (ref "JA5") (pin "69") (pinfunction "69_69") (pintype "bidirectional"))
    )
    (net (code "78") (name "unconnected-(JA7-Pad34)") (class "Default")
      (node (ref "JA7") (pin "34") (pinfunction "34_34") (pintype "bidirectional"))
    )
    (net (code "79") (name "unconnected-(JA7-Pad35)") (class "Default")
      (node (ref "JA7") (pin "35") (pinfunction "35_35") (pintype "bidirectional"))
    )
    (net (code "80") (name "unconnected-(JA7-Pad36)") (class "Default")
      (node (ref "JA7") (pin "36") (pinfunction "36_36") (pintype "bidirectional"))
    )
    (net (code "81") (name "unconnected-(JA7-Pad69)") (class "Default")
      (node (ref "JA7") (pin "69") (pinfunction "69_69") (pintype "bidirectional"))
    )
  )
)
